# cs42448_breakout.net
KiCad netlist of a schematic drawn in Altium Designer
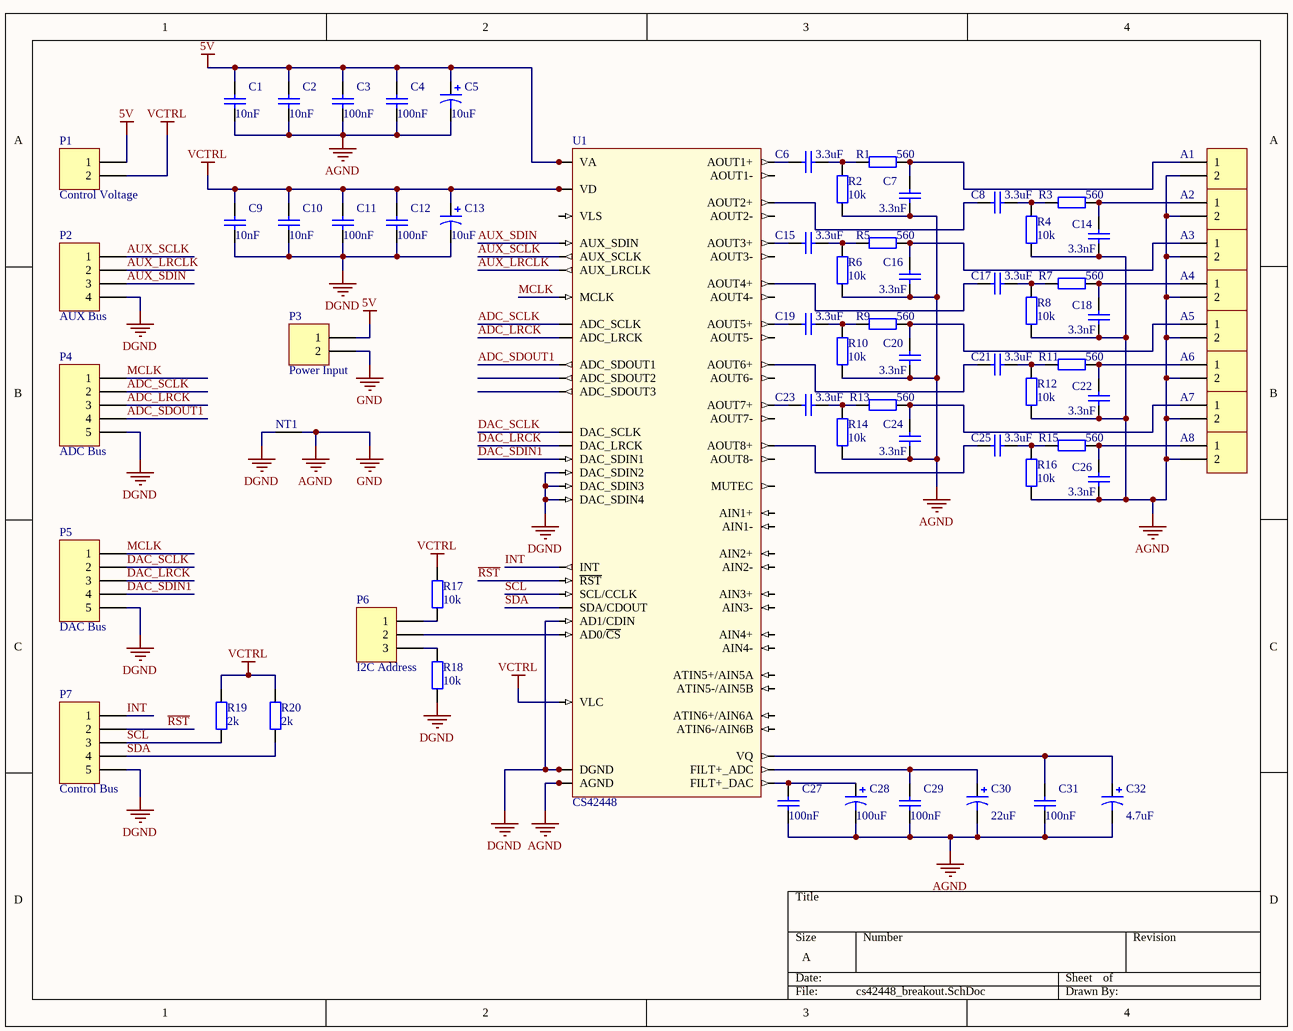
[diagram p0: cs42448_breakout.SchDoc]

(export (version "E")
  (design (tool "Eeschema 10.0.6"))
  (components
    (comp (ref "A1")
      (value "Header 2")
      (footprint "HDR1X2")
      (description "Header, 2-Pin")
      (fields (field (name "PUBLISHER") "Altium Limited"))
      (libsource (lib "") (part "Header 2_1"))
    )
    (comp (ref "A2")
      (value "Header 2")
      (footprint "HDR1X2")
      (description "Header, 2-Pin")
      (fields (field (name "PUBLISHER") "Altium Limited"))
      (libsource (lib "") (part "Header 2_1"))
    )
    (comp (ref "A3")
      (value "Header 2")
      (footprint "HDR1X2")
      (description "Header, 2-Pin")
      (fields (field (name "PUBLISHER") "Altium Limited"))
      (libsource (lib "") (part "Header 2_1"))
    )
    (comp (ref "A4")
      (value "Header 2")
      (footprint "HDR1X2")
      (description "Header, 2-Pin")
      (fields (field (name "PUBLISHER") "Altium Limited"))
      (libsource (lib "") (part "Header 2_1"))
    )
    (comp (ref "A5")
      (value "Header 2")
      (footprint "HDR1X2")
      (description "Header, 2-Pin")
      (fields (field (name "PUBLISHER") "Altium Limited"))
      (libsource (lib "") (part "Header 2_1"))
    )
    (comp (ref "A6")
      (value "Header 2")
      (footprint "HDR1X2")
      (description "Header, 2-Pin")
      (fields (field (name "PUBLISHER") "Altium Limited"))
      (libsource (lib "") (part "Header 2_1"))
    )
    (comp (ref "A7")
      (value "Header 2")
      (footprint "HDR1X2")
      (description "Header, 2-Pin")
      (fields (field (name "PUBLISHER") "Altium Limited"))
      (libsource (lib "") (part "Header 2_1"))
    )
    (comp (ref "A8")
      (value "Header 2")
      (footprint "HDR1X2")
      (description "Header, 2-Pin")
      (fields (field (name "PUBLISHER") "Altium Limited"))
      (libsource (lib "") (part "Header 2_1"))
    )
    (comp (ref "C1")
      (value "10nF")
      (footprint "1608[0603]")
      (description "Capacitor")
      (fields (field (name "Comment") "Cap") (field (name "PUBLISHER") "Altium Limited"))
      (libsource (lib "Miscellaneous Devices") (part "Cap"))
    )
    (comp (ref "C2")
      (value "10nF")
      (footprint "1608[0603]")
      (description "Capacitor")
      (fields (field (name "Comment") "Cap") (field (name "PUBLISHER") "Altium Limited"))
      (libsource (lib "Miscellaneous Devices") (part "Cap"))
    )
    (comp (ref "C3")
      (value "100nF")
      (footprint "1608[0603]")
      (description "Capacitor")
      (fields (field (name "Comment") "Cap") (field (name "PUBLISHER") "Altium Limited"))
      (libsource (lib "Miscellaneous Devices") (part "Cap"))
    )
    (comp (ref "C4")
      (value "100nF")
      (footprint "1608[0603]")
      (description "Capacitor")
      (fields (field (name "Comment") "Cap") (field (name "PUBLISHER") "Altium Limited"))
      (libsource (lib "Miscellaneous Devices") (part "Cap"))
    )
    (comp (ref "C5")
      (value "10uF")
      (footprint "Miscellaneous Devices:CAPR5-4X5")
      (description "Polarized Capacitor (Radial)")
      (fields (field (name "Comment") "Cap Pol1") (field (name "PUBLISHER") "Altium Limited"))
      (libsource (lib "Miscellaneous Devices") (part "Cap Pol1"))
    )
    (comp (ref "C6")
      (value "3.3uF")
      (footprint "1608[0603]")
      (description "Capacitor")
      (fields (field (name "Comment") "Cap") (field (name "PUBLISHER") "Altium Limited"))
      (libsource (lib "Miscellaneous Devices") (part "Cap"))
    )
    (comp (ref "C7")
      (value "3.3nF")
      (footprint "1608[0603]")
      (description "Capacitor")
      (fields (field (name "Comment") "Cap") (field (name "PUBLISHER") "Altium Limited"))
      (libsource (lib "Miscellaneous Devices") (part "Cap"))
    )
    (comp (ref "C8")
      (value "3.3uF")
      (footprint "1608[0603]")
      (description "Capacitor")
      (fields (field (name "Comment") "Cap") (field (name "PUBLISHER") "Altium Limited"))
      (libsource (lib "Miscellaneous Devices") (part "Cap"))
    )
    (comp (ref "C9")
      (value "10nF")
      (footprint "1608[0603]")
      (description "Capacitor")
      (fields (field (name "Comment") "Cap") (field (name "PUBLISHER") "Altium Limited"))
      (libsource (lib "Miscellaneous Devices") (part "Cap"))
    )
    (comp (ref "C10")
      (value "10nF")
      (footprint "1608[0603]")
      (description "Capacitor")
      (fields (field (name "Comment") "Cap") (field (name "PUBLISHER") "Altium Limited"))
      (libsource (lib "Miscellaneous Devices") (part "Cap"))
    )
    (comp (ref "C11")
      (value "100nF")
      (footprint "1608[0603]")
      (description "Capacitor")
      (fields (field (name "Comment") "Cap") (field (name "PUBLISHER") "Altium Limited"))
      (libsource (lib "Miscellaneous Devices") (part "Cap"))
    )
    (comp (ref "C12")
      (value "100nF")
      (footprint "1608[0603]")
      (description "Capacitor")
      (fields (field (name "Comment") "Cap") (field (name "PUBLISHER") "Altium Limited"))
      (libsource (lib "Miscellaneous Devices") (part "Cap"))
    )
    (comp (ref "C13")
      (value "10uF")
      (footprint "Miscellaneous Devices:CAPR5-4X5")
      (description "Polarized Capacitor (Radial)")
      (fields (field (name "Comment") "Cap Pol1") (field (name "PUBLISHER") "Altium Limited"))
      (libsource (lib "Miscellaneous Devices") (part "Cap Pol1"))
    )
    (comp (ref "C14")
      (value "3.3nF")
      (footprint "1608[0603]")
      (description "Capacitor")
      (fields (field (name "Comment") "Cap") (field (name "PUBLISHER") "Altium Limited"))
      (libsource (lib "Miscellaneous Devices") (part "Cap"))
    )
    (comp (ref "C15")
      (value "3.3uF")
      (footprint "1608[0603]")
      (description "Capacitor")
      (fields (field (name "Comment") "Cap") (field (name "PUBLISHER") "Altium Limited"))
      (libsource (lib "Miscellaneous Devices") (part "Cap"))
    )
    (comp (ref "C16")
      (value "3.3nF")
      (footprint "1608[0603]")
      (description "Capacitor")
      (fields (field (name "Comment") "Cap") (field (name "PUBLISHER") "Altium Limited"))
      (libsource (lib "Miscellaneous Devices") (part "Cap"))
    )
    (comp (ref "C17")
      (value "3.3uF")
      (footprint "1608[0603]")
      (description "Capacitor")
      (fields (field (name "Comment") "Cap") (field (name "PUBLISHER") "Altium Limited"))
      (libsource (lib "Miscellaneous Devices") (part "Cap"))
    )
    (comp (ref "C18")
      (value "3.3nF")
      (footprint "1608[0603]")
      (description "Capacitor")
      (fields (field (name "Comment") "Cap") (field (name "PUBLISHER") "Altium Limited"))
      (libsource (lib "Miscellaneous Devices") (part "Cap"))
    )
    (comp (ref "C19")
      (value "3.3uF")
      (footprint "1608[0603]")
      (description "Capacitor")
      (fields (field (name "Comment") "Cap") (field (name "PUBLISHER") "Altium Limited"))
      (libsource (lib "Miscellaneous Devices") (part "Cap"))
    )
    (comp (ref "C20")
      (value "3.3nF")
      (footprint "1608[0603]")
      (description "Capacitor")
      (fields (field (name "Comment") "Cap") (field (name "PUBLISHER") "Altium Limited"))
      (libsource (lib "Miscellaneous Devices") (part "Cap"))
    )
    (comp (ref "C21")
      (value "3.3uF")
      (footprint "1608[0603]")
      (description "Capacitor")
      (fields (field (name "Comment") "Cap") (field (name "PUBLISHER") "Altium Limited"))
      (libsource (lib "Miscellaneous Devices") (part "Cap"))
    )
    (comp (ref "C22")
      (value "3.3nF")
      (footprint "1608[0603]")
      (description "Capacitor")
      (fields (field (name "Comment") "Cap") (field (name "PUBLISHER") "Altium Limited"))
      (libsource (lib "Miscellaneous Devices") (part "Cap"))
    )
    (comp (ref "C23")
      (value "3.3uF")
      (footprint "1608[0603]")
      (description "Capacitor")
      (fields (field (name "Comment") "Cap") (field (name "PUBLISHER") "Altium Limited"))
      (libsource (lib "Miscellaneous Devices") (part "Cap"))
    )
    (comp (ref "C24")
      (value "3.3nF")
      (footprint "1608[0603]")
      (description "Capacitor")
      (fields (field (name "Comment") "Cap") (field (name "PUBLISHER") "Altium Limited"))
      (libsource (lib "Miscellaneous Devices") (part "Cap"))
    )
    (comp (ref "C25")
      (value "3.3uF")
      (footprint "1608[0603]")
      (description "Capacitor")
      (fields (field (name "Comment") "Cap") (field (name "PUBLISHER") "Altium Limited"))
      (libsource (lib "Miscellaneous Devices") (part "Cap"))
    )
    (comp (ref "C26")
      (value "3.3nF")
      (footprint "1608[0603]")
      (description "Capacitor")
      (fields (field (name "Comment") "Cap") (field (name "PUBLISHER") "Altium Limited"))
      (libsource (lib "Miscellaneous Devices") (part "Cap"))
    )
    (comp (ref "C27")
      (value "100nF")
      (footprint "1608[0603]")
      (description "Capacitor")
      (fields (field (name "Comment") "Cap") (field (name "PUBLISHER") "Altium Limited"))
      (libsource (lib "Miscellaneous Devices") (part "Cap"))
    )
    (comp (ref "C28")
      (value "100uF")
      (footprint "Miscellaneous Devices:CAPR5-4X5")
      (description "Polarized Capacitor (Radial)")
      (fields (field (name "Comment") "Cap Pol1") (field (name "PUBLISHER") "Altium Limited"))
      (libsource (lib "Miscellaneous Devices") (part "Cap Pol1"))
    )
    (comp (ref "C29")
      (value "100nF")
      (footprint "1608[0603]")
      (description "Capacitor")
      (fields (field (name "Comment") "Cap") (field (name "PUBLISHER") "Altium Limited"))
      (libsource (lib "Miscellaneous Devices") (part "Cap"))
    )
    (comp (ref "C30")
      (value "22uF")
      (footprint "Miscellaneous Devices:CAPR5-4X5")
      (description "Polarized Capacitor (Radial)")
      (fields (field (name "Comment") "Cap Pol1") (field (name "PUBLISHER") "Altium Limited"))
      (libsource (lib "Miscellaneous Devices") (part "Cap Pol1"))
    )
    (comp (ref "C31")
      (value "100nF")
      (footprint "1608[0603]")
      (description "Capacitor")
      (fields (field (name "Comment") "Cap") (field (name "PUBLISHER") "Altium Limited"))
      (libsource (lib "Miscellaneous Devices") (part "Cap"))
    )
    (comp (ref "C32")
      (value "4.7uF")
      (footprint "Miscellaneous Devices:CAPR5-4X5")
      (description "Polarized Capacitor (Radial)")
      (fields (field (name "Comment") "Cap Pol1") (field (name "PUBLISHER") "Altium Limited"))
      (libsource (lib "Miscellaneous Devices") (part "Cap Pol1"))
    )
    (comp (ref "NT1")
      (value "Net Tie")
      (footprint "1608[0603] Net Tie")
      (libsource (lib "cs42448_breakout") (part "Net Tie"))
    )
    (comp (ref "P1")
      (value "Control Voltage")
      (footprint "HDR1X2")
      (description "Header, 2-Pin")
      (fields (field (name "PUBLISHER") "Altium Limited"))
      (libsource (lib "Miscellaneous Connectors") (part "Header 2"))
    )
    (comp (ref "P2")
      (value "AUX Bus")
      (footprint "HDR1X4")
      (description "Header, 4-Pin")
      (fields (field (name "PUBLISHER") "Altium Limited"))
      (libsource (lib "Miscellaneous Connectors") (part "Header 4"))
    )
    (comp (ref "P3")
      (value "Power Input")
      (footprint "HDR1X2")
      (description "Header, 2-Pin")
      (fields (field (name "PUBLISHER") "Altium Limited"))
      (libsource (lib "Miscellaneous Connectors") (part "Header 2"))
    )
    (comp (ref "P4")
      (value "ADC Bus")
      (footprint "HDR1X5")
      (description "Header, 5-Pin")
      (fields (field (name "PUBLISHER") "Altium Limited"))
      (libsource (lib "Miscellaneous Connectors") (part "Header 5"))
    )
    (comp (ref "P5")
      (value "DAC Bus")
      (footprint "HDR1X5")
      (description "Header, 5-Pin")
      (fields (field (name "PUBLISHER") "Altium Limited"))
      (libsource (lib "Miscellaneous Connectors") (part "Header 5"))
    )
    (comp (ref "P6")
      (value "I2C Address")
      (footprint "HDR1X3")
      (description "Header, 3-Pin")
      (fields (field (name "PUBLISHER") "Altium Limited"))
      (libsource (lib "Miscellaneous Connectors") (part "Header 3"))
    )
    (comp (ref "P7")
      (value "Control Bus")
      (footprint "HDR1X5")
      (description "Header, 5-Pin")
      (fields (field (name "PUBLISHER") "Altium Limited"))
      (libsource (lib "Miscellaneous Connectors") (part "Header 5"))
    )
    (comp (ref "R1")
      (value "560")
      (footprint "1608[0603]")
      (description "Resistor")
      (fields (field (name "Comment") "Res2") (field (name "PUBLISHER") "Altium Limited"))
      (libsource (lib "") (part "Res2_1"))
    )
    (comp (ref "R2")
      (value "10k")
      (footprint "1608[0603]")
      (description "Resistor")
      (fields (field (name "Comment") "Res2") (field (name "PUBLISHER") "Altium Limited"))
      (libsource (lib "Miscellaneous Devices") (part "Res2"))
    )
    (comp (ref "R3")
      (value "560")
      (footprint "1608[0603]")
      (description "Resistor")
      (fields (field (name "Comment") "Res2") (field (name "PUBLISHER") "Altium Limited"))
      (libsource (lib "") (part "Res2_1"))
    )
    (comp (ref "R4")
      (value "10k")
      (footprint "1608[0603]")
      (description "Resistor")
      (fields (field (name "Comment") "Res2") (field (name "PUBLISHER") "Altium Limited"))
      (libsource (lib "Miscellaneous Devices") (part "Res2"))
    )
    (comp (ref "R5")
      (value "560")
      (footprint "1608[0603]")
      (description "Resistor")
      (fields (field (name "Comment") "Res2") (field (name "PUBLISHER") "Altium Limited"))
      (libsource (lib "") (part "Res2_1"))
    )
    (comp (ref "R6")
      (value "10k")
      (footprint "1608[0603]")
      (description "Resistor")
      (fields (field (name "Comment") "Res2") (field (name "PUBLISHER") "Altium Limited"))
      (libsource (lib "Miscellaneous Devices") (part "Res2"))
    )
    (comp (ref "R7")
      (value "560")
      (footprint "1608[0603]")
      (description "Resistor")
      (fields (field (name "Comment") "Res2") (field (name "PUBLISHER") "Altium Limited"))
      (libsource (lib "") (part "Res2_1"))
    )
    (comp (ref "R8")
      (value "10k")
      (footprint "1608[0603]")
      (description "Resistor")
      (fields (field (name "Comment") "Res2") (field (name "PUBLISHER") "Altium Limited"))
      (libsource (lib "Miscellaneous Devices") (part "Res2"))
    )
    (comp (ref "R9")
      (value "560")
      (footprint "1608[0603]")
      (description "Resistor")
      (fields (field (name "Comment") "Res2") (field (name "PUBLISHER") "Altium Limited"))
      (libsource (lib "") (part "Res2_1"))
    )
    (comp (ref "R10")
      (value "10k")
      (footprint "1608[0603]")
      (description "Resistor")
      (fields (field (name "Comment") "Res2") (field (name "PUBLISHER") "Altium Limited"))
      (libsource (lib "Miscellaneous Devices") (part "Res2"))
    )
    (comp (ref "R11")
      (value "560")
      (footprint "1608[0603]")
      (description "Resistor")
      (fields (field (name "Comment") "Res2") (field (name "PUBLISHER") "Altium Limited"))
      (libsource (lib "") (part "Res2_1"))
    )
    (comp (ref "R12")
      (value "10k")
      (footprint "1608[0603]")
      (description "Resistor")
      (fields (field (name "Comment") "Res2") (field (name "PUBLISHER") "Altium Limited"))
      (libsource (lib "Miscellaneous Devices") (part "Res2"))
    )
    (comp (ref "R13")
      (value "560")
      (footprint "1608[0603]")
      (description "Resistor")
      (fields (field (name "Comment") "Res2") (field (name "PUBLISHER") "Altium Limited"))
      (libsource (lib "") (part "Res2_1"))
    )
    (comp (ref "R14")
      (value "10k")
      (footprint "1608[0603]")
      (description "Resistor")
      (fields (field (name "Comment") "Res2") (field (name "PUBLISHER") "Altium Limited"))
      (libsource (lib "Miscellaneous Devices") (part "Res2"))
    )
    (comp (ref "R15")
      (value "560")
      (footprint "1608[0603]")
      (description "Resistor")
      (fields (field (name "Comment") "Res2") (field (name "PUBLISHER") "Altium Limited"))
      (libsource (lib "") (part "Res2_1"))
    )
    (comp (ref "R16")
      (value "10k")
      (footprint "1608[0603]")
      (description "Resistor")
      (fields (field (name "Comment") "Res2") (field (name "PUBLISHER") "Altium Limited"))
      (libsource (lib "Miscellaneous Devices") (part "Res2"))
    )
    (comp (ref "R17")
      (value "10k")
      (footprint "1608[0603]")
      (description "Resistor")
      (fields (field (name "Comment") "Res2") (field (name "PUBLISHER") "Altium Limited"))
      (libsource (lib "Miscellaneous Devices") (part "Res2"))
    )
    (comp (ref "R18")
      (value "10k")
      (footprint "1608[0603]")
      (description "Resistor")
      (fields (field (name "Comment") "Res2") (field (name "PUBLISHER") "Altium Limited"))
      (libsource (lib "Miscellaneous Devices") (part "Res2"))
    )
    (comp (ref "R19")
      (value "2k")
      (footprint "1608[0603]")
      (description "Resistor")
      (fields (field (name "Comment") "Res2") (field (name "PUBLISHER") "Altium Limited"))
      (libsource (lib "Miscellaneous Devices") (part "Res2"))
    )
    (comp (ref "R20")
      (value "2k")
      (footprint "1608[0603]")
      (description "Resistor")
      (fields (field (name "Comment") "Res2") (field (name "PUBLISHER") "Altium Limited"))
      (libsource (lib "Miscellaneous Devices") (part "Res2"))
    )
    (comp (ref "U1")
      (value "CS42448")
      (footprint "64L-LQFP")
      (description "108 dB, 192 kHz 6-In, 8-Out CODEC")
      (libsource (lib "cs42448_breakout") (part "CS42448"))
    )
  )
  (nets
    (net (code "1") (name "/ADC_LRCK") (class "Default")
      (node (ref "P4") (pin "3") (pinfunction "3_3") (pintype "passive"))
      (node (ref "U1") (pin "5") (pinfunction "ADC_LRCK_5") (pintype "bidirectional"))
    )
    (net (code "2") (name "/ADC_SCLK") (class "Default")
      (node (ref "P4") (pin "2") (pinfunction "2_2") (pintype "passive"))
      (node (ref "U1") (pin "9") (pinfunction "ADC_SCLK_9") (pintype "bidirectional"))
    )
    (net (code "3") (name "/ADC_SDOUT1") (class "Default")
      (node (ref "P4") (pin "4") (pinfunction "4_4") (pintype "passive"))
      (node (ref "U1") (pin "13") (pinfunction "ADC_SDOUT1_13") (pintype "output"))
    )
    (net (code "4") (name "/AUX_LRCLK") (class "Default")
      (node (ref "P2") (pin "2") (pinfunction "2_2") (pintype "passive"))
      (node (ref "U1") (pin "20") (pinfunction "AUX_LRCLK_20") (pintype "output"))
    )
    (net (code "5") (name "/AUX_SCLK") (class "Default")
      (node (ref "P2") (pin "1") (pinfunction "1_1") (pintype "passive"))
      (node (ref "U1") (pin "21") (pinfunction "AUX_SCLK_21") (pintype "output"))
    )
    (net (code "6") (name "/AUX_SDIN") (class "Default")
      (node (ref "P2") (pin "3") (pinfunction "3_3") (pintype "passive"))
      (node (ref "U1") (pin "22") (pinfunction "AUX_SDIN_22") (pintype "input"))
    )
    (net (code "7") (name "/DAC_LRCK") (class "Default")
      (node (ref "P5") (pin "3") (pinfunction "3_3") (pintype "passive"))
      (node (ref "U1") (pin "19") (pinfunction "DAC_LRCK_19") (pintype "bidirectional"))
    )
    (net (code "8") (name "/DAC_SCLK") (class "Default")
      (node (ref "P5") (pin "2") (pinfunction "2_2") (pintype "passive"))
      (node (ref "U1") (pin "18") (pinfunction "DAC_SCLK_18") (pintype "bidirectional"))
    )
    (net (code "9") (name "/DAC_SDIN1") (class "Default")
      (node (ref "P5") (pin "4") (pinfunction "4_4") (pintype "passive"))
      (node (ref "U1") (pin "17") (pinfunction "DAC_SDIN1_17") (pintype "input"))
    )
    (net (code "10") (name "/INT") (class "Default")
      (node (ref "P7") (pin "1") (pinfunction "1_1") (pintype "passive"))
      (node (ref "U1") (pin "61") (pinfunction "INT_61") (pintype "output"))
    )
    (net (code "11") (name "/MCLK") (class "Default")
      (node (ref "P4") (pin "1") (pinfunction "1_1") (pintype "passive"))
      (node (ref "P5") (pin "1") (pinfunction "1_1") (pintype "passive"))
      (node (ref "U1") (pin "10") (pinfunction "MCLK_10") (pintype "input"))
    )
    (net (code "12") (name "/SCL") (class "Default")
      (node (ref "P7") (pin "3") (pinfunction "3_3") (pintype "passive"))
      (node (ref "R19") (pin "2") (pinfunction "2_2") (pintype "passive"))
      (node (ref "U1") (pin "63") (pinfunction "SCL/CCLK_63") (pintype "input"))
    )
    (net (code "13") (name "/SDA") (class "Default")
      (node (ref "P7") (pin "4") (pinfunction "4_4") (pintype "passive"))
      (node (ref "R20") (pin "2") (pinfunction "2_2") (pintype "passive"))
      (node (ref "U1") (pin "64") (pinfunction "SDA/CDOUT_64") (pintype "bidirectional"))
    )
    (net (code "14") (name "/~{RST}") (class "Default")
      (node (ref "P7") (pin "2") (pinfunction "2_2") (pintype "passive"))
      (node (ref "U1") (pin "3") (pinfunction "~{RST}_3") (pintype "input"))
    )
    (net (code "15") (name "5V") (class "Default")
      (node (ref "C1") (pin "2") (pinfunction "2_2") (pintype "passive"))
      (node (ref "C2") (pin "2") (pinfunction "2_2") (pintype "passive"))
      (node (ref "C3") (pin "2") (pinfunction "2_2") (pintype "passive"))
      (node (ref "C4") (pin "2") (pinfunction "2_2") (pintype "passive"))
      (node (ref "C5") (pin "1") (pinfunction "1_1") (pintype "passive"))
      (node (ref "P1") (pin "1") (pinfunction "1_1") (pintype "passive"))
      (node (ref "P3") (pin "1") (pinfunction "1_1") (pintype "passive"))
      (node (ref "U1") (pin "44") (pinfunction "VA_44") (pintype "power_in"))
      (node (ref "U1") (pin "53") (pinfunction "VA_53") (pintype "power_in"))
    )
    (net (code "16") (name "AGND") (class "Default")
      (node (ref "A1") (pin "2") (pinfunction "2_2") (pintype "passive"))
      (node (ref "A2") (pin "2") (pinfunction "2_2") (pintype "passive"))
      (node (ref "A3") (pin "2") (pinfunction "2_2") (pintype "passive"))
      (node (ref "A4") (pin "2") (pinfunction "2_2") (pintype "passive"))
      (node (ref "A5") (pin "2") (pinfunction "2_2") (pintype "passive"))
      (node (ref "A6") (pin "2") (pinfunction "2_2") (pintype "passive"))
      (node (ref "A7") (pin "2") (pinfunction "2_2") (pintype "passive"))
      (node (ref "A8") (pin "2") (pinfunction "2_2") (pintype "passive"))
      (node (ref "C1") (pin "1") (pinfunction "1_1") (pintype "passive"))
      (node (ref "C14") (pin "1") (pinfunction "1_1") (pintype "passive"))
      (node (ref "C16") (pin "1") (pinfunction "1_1") (pintype "passive"))
      (node (ref "C18") (pin "1") (pinfunction "1_1") (pintype "passive"))
      (node (ref "C2") (pin "1") (pinfunction "1_1") (pintype "passive"))
      (node (ref "C20") (pin "1") (pinfunction "1_1") (pintype "passive"))
      (node (ref "C22") (pin "1") (pinfunction "1_1") (pintype "passive"))
      (node (ref "C24") (pin "1") (pinfunction "1_1") (pintype "passive"))
      (node (ref "C26") (pin "1") (pinfunction "1_1") (pintype "passive"))
      (node (ref "C27") (pin "1") (pinfunction "1_1") (pintype "passive"))
      (node (ref "C28") (pin "2") (pinfunction "2_2") (pintype "passive"))
      (node (ref "C29") (pin "1") (pinfunction "1_1") (pintype "passive"))
      (node (ref "C3") (pin "1") (pinfunction "1_1") (pintype "passive"))
      (node (ref "C30") (pin "2") (pinfunction "2_2") (pintype "passive"))
      (node (ref "C31") (pin "1") (pinfunction "1_1") (pintype "passive"))
      (node (ref "C32") (pin "2") (pinfunction "2_2") (pintype "passive"))
      (node (ref "C4") (pin "1") (pinfunction "1_1") (pintype "passive"))
      (node (ref "C5") (pin "2") (pinfunction "2_2") (pintype "passive"))
      (node (ref "C7") (pin "1") (pinfunction "1_1") (pintype "passive"))
      (node (ref "NT1") (pin "2") (pinfunction "2_2") (pintype "passive"))
      (node (ref "P3") (pin "2") (pinfunction "2_2") (pintype "passive"))
      (node (ref "R10") (pin "2") (pinfunction "2_2") (pintype "passive"))
      (node (ref "R12") (pin "2") (pinfunction "2_2") (pintype "passive"))
      (node (ref "R14") (pin "2") (pinfunction "2_2") (pintype "passive"))
      (node (ref "R16") (pin "2") (pinfunction "2_2") (pintype "passive"))
      (node (ref "R2") (pin "2") (pinfunction "2_2") (pintype "passive"))
      (node (ref "R4") (pin "2") (pinfunction "2_2") (pintype "passive"))
      (node (ref "R6") (pin "2") (pinfunction "2_2") (pintype "passive"))
      (node (ref "R8") (pin "2") (pinfunction "2_2") (pintype "passive"))
      (node (ref "U1") (pin "42") (pinfunction "AGND_42") (pintype "power_in"))
      (node (ref "U1") (pin "56") (pinfunction "AGND_56") (pintype "power_in"))
    )
    (net (code "17") (name "DGND") (class "Default")
      (node (ref "C10") (pin "1") (pinfunction "1_1") (pintype "passive"))
      (node (ref "C11") (pin "1") (pinfunction "1_1") (pintype "passive"))
      (node (ref "C12") (pin "1") (pinfunction "1_1") (pintype "passive"))
      (node (ref "C13") (pin "2") (pinfunction "2_2") (pintype "passive"))
      (node (ref "C9") (pin "1") (pinfunction "1_1") (pintype "passive"))
      (node (ref "NT1") (pin "1") (pintype "passive"))
      (node (ref "P2") (pin "4") (pinfunction "4_4") (pintype "passive"))
      (node (ref "P4") (pin "5") (pinfunction "5_5") (pintype "passive"))
      (node (ref "P5") (pin "5") (pinfunction "5_5") (pintype "passive"))
      (node (ref "P7") (pin "5") (pinfunction "5_5") (pintype "passive"))
      (node (ref "R18") (pin "2") (pinfunction "2_2") (pintype "passive"))
      (node (ref "U1") (pin "14") (pinfunction "DAC_SDIN4_14") (pintype "input"))
      (node (ref "U1") (pin "15") (pinfunction "DAC_SDIN3_15") (pintype "input"))
      (node (ref "U1") (pin "16") (pinfunction "DAC_SDIN2_16") (pintype "input"))
      (node (ref "U1") (pin "2") (pinfunction "AD1/CDIN_2") (pintype "input"))
      (node (ref "U1") (pin "23") (pinfunction "DGND_23") (pintype "power_in"))
      (node (ref "U1") (pin "62") (pinfunction "DGND_62") (pintype "power_in"))
      (node (ref "U1") (pin "7") (pinfunction "DGND_7") (pintype "power_in"))
    )
    (net (code "18") (name "Net-(A1-Pad1)") (class "Default")
      (node (ref "A1") (pin "1") (pinfunction "1_1") (pintype "passive"))
      (node (ref "C7") (pin "2") (pinfunction "2_2") (pintype "passive"))
      (node (ref "R1") (pin "1") (pinfunction "1_1") (pintype "passive"))
    )
    (net (code "19") (name "Net-(A2-Pad1)") (class "Default")
      (node (ref "A2") (pin "1") (pinfunction "1_1") (pintype "passive"))
      (node (ref "C14") (pin "2") (pinfunction "2_2") (pintype "passive"))
      (node (ref "R3") (pin "1") (pinfunction "1_1") (pintype "passive"))
    )
    (net (code "20") (name "Net-(A3-Pad1)") (class "Default")
      (node (ref "A3") (pin "1") (pinfunction "1_1") (pintype "passive"))
      (node (ref "C16") (pin "2") (pinfunction "2_2") (pintype "passive"))
      (node (ref "R5") (pin "1") (pinfunction "1_1") (pintype "passive"))
    )
    (net (code "21") (name "Net-(A4-Pad1)") (class "Default")
      (node (ref "A4") (pin "1") (pinfunction "1_1") (pintype "passive"))
      (node (ref "C18") (pin "2") (pinfunction "2_2") (pintype "passive"))
      (node (ref "R7") (pin "1") (pinfunction "1_1") (pintype "passive"))
    )
    (net (code "22") (name "Net-(A5-Pad1)") (class "Default")
      (node (ref "A5") (pin "1") (pinfunction "1_1") (pintype "passive"))
      (node (ref "C20") (pin "2") (pinfunction "2_2") (pintype "passive"))
      (node (ref "R9") (pin "1") (pinfunction "1_1") (pintype "passive"))
    )
    (net (code "23") (name "Net-(A6-Pad1)") (class "Default")
      (node (ref "A6") (pin "1") (pinfunction "1_1") (pintype "passive"))
      (node (ref "C22") (pin "2") (pinfunction "2_2") (pintype "passive"))
      (node (ref "R11") (pin "1") (pinfunction "1_1") (pintype "passive"))
    )
    (net (code "24") (name "Net-(A7-Pad1)") (class "Default")
      (node (ref "A7") (pin "1") (pinfunction "1_1") (pintype "passive"))
      (node (ref "C24") (pin "2") (pinfunction "2_2") (pintype "passive"))
      (node (ref "R13") (pin "1") (pinfunction "1_1") (pintype "passive"))
    )
    (net (code "25") (name "Net-(A8-Pad1)") (class "Default")
      (node (ref "A8") (pin "1") (pinfunction "1_1") (pintype "passive"))
      (node (ref "C26") (pin "2") (pinfunction "2_2") (pintype "passive"))
      (node (ref "R15") (pin "1") (pinfunction "1_1") (pintype "passive"))
    )
    (net (code "26") (name "Net-(C6-Pad1)") (class "Default")
      (node (ref "C6") (pin "1") (pinfunction "1_1") (pintype "passive"))
      (node (ref "R1") (pin "2") (pinfunction "2_2") (pintype "passive"))
      (node (ref "R2") (pin "1") (pinfunction "1_1") (pintype "passive"))
    )
    (net (code "27") (name "Net-(C8-Pad1)") (class "Default")
      (node (ref "C8") (pin "1") (pinfunction "1_1") (pintype "passive"))
      (node (ref "R3") (pin "2") (pinfunction "2_2") (pintype "passive"))
      (node (ref "R4") (pin "1") (pinfunction "1_1") (pintype "passive"))
    )
    (net (code "28") (name "Net-(C15-Pad1)") (class "Default")
      (node (ref "C15") (pin "1") (pinfunction "1_1") (pintype "passive"))
      (node (ref "R5") (pin "2") (pinfunction "2_2") (pintype "passive"))
      (node (ref "R6") (pin "1") (pinfunction "1_1") (pintype "passive"))
    )
    (net (code "29") (name "Net-(C17-Pad1)") (class "Default")
      (node (ref "C17") (pin "1") (pinfunction "1_1") (pintype "passive"))
      (node (ref "R7") (pin "2") (pinfunction "2_2") (pintype "passive"))
      (node (ref "R8") (pin "1") (pinfunction "1_1") (pintype "passive"))
    )
    (net (code "30") (name "Net-(C19-Pad1)") (class "Default")
      (node (ref "C19") (pin "1") (pinfunction "1_1") (pintype "passive"))
      (node (ref "R10") (pin "1") (pinfunction "1_1") (pintype "passive"))
      (node (ref "R9") (pin "2") (pinfunction "2_2") (pintype "passive"))
    )
    (net (code "31") (name "Net-(C21-Pad1)") (class "Default")
      (node (ref "C21") (pin "1") (pinfunction "1_1") (pintype "passive"))
      (node (ref "R11") (pin "2") (pinfunction "2_2") (pintype "passive"))
      (node (ref "R12") (pin "1") (pinfunction "1_1") (pintype "passive"))
    )
    (net (code "32") (name "Net-(C23-Pad1)") (class "Default")
      (node (ref "C23") (pin "1") (pinfunction "1_1") (pintype "passive"))
      (node (ref "R13") (pin "2") (pinfunction "2_2") (pintype "passive"))
      (node (ref "R14") (pin "1") (pinfunction "1_1") (pintype "passive"))
    )
    (net (code "33") (name "Net-(C25-Pad1)") (class "Default")
      (node (ref "C25") (pin "1") (pinfunction "1_1") (pintype "passive"))
      (node (ref "R15") (pin "2") (pinfunction "2_2") (pintype "passive"))
      (node (ref "R16") (pin "1") (pinfunction "1_1") (pintype "passive"))
    )
    (net (code "34") (name "Net-(P6-Pad1)") (class "Default")
      (node (ref "P6") (pin "1") (pinfunction "1_1") (pintype "passive"))
      (node (ref "R17") (pin "2") (pinfunction "2_2") (pintype "passive"))
    )
    (net (code "35") (name "Net-(P6-Pad3)") (class "Default")
      (node (ref "P6") (pin "3") (pinfunction "3_3") (pintype "passive"))
      (node (ref "R18") (pin "1") (pinfunction "1_1") (pintype "passive"))
    )
    (net (code "36") (name "Net-(U1-AD0{slash}~{CS})") (class "Default")
      (node (ref "P6") (pin "2") (pinfunction "2_2") (pintype "passive"))
      (node (ref "U1") (pin "1") (pinfunction "AD0/~{CS}_1") (pintype "input"))
    )
    (net (code "37") (name "Net-(U1-AOUT1+)") (class "Default")
      (node (ref "C6") (pin "2") (pinfunction "2_2") (pintype "passive"))
      (node (ref "U1") (pin "26") (pinfunction "AOUT1+_26") (pintype "output"))
    )
    (net (code "38") (name "Net-(U1-AOUT2+)") (class "Default")
      (node (ref "C8") (pin "2") (pinfunction "2_2") (pintype "passive"))
      (node (ref "U1") (pin "27") (pinfunction "AOUT2+_27") (pintype "output"))
    )
    (net (code "39") (name "Net-(U1-AOUT3+)") (class "Default")
      (node (ref "C15") (pin "2") (pinfunction "2_2") (pintype "passive"))
      (node (ref "U1") (pin "30") (pinfunction "AOUT3+_30") (pintype "output"))
    )
    (net (code "40") (name "Net-(U1-AOUT4+)") (class "Default")
      (node (ref "C17") (pin "2") (pinfunction "2_2") (pintype "passive"))
      (node (ref "U1") (pin "31") (pinfunction "AOUT4+_31") (pintype "output"))
    )
    (net (code "41") (name "Net-(U1-AOUT5+)") (class "Default")
      (node (ref "C19") (pin "2") (pinfunction "2_2") (pintype "passive"))
      (node (ref "U1") (pin "34") (pinfunction "AOUT5+_34") (pintype "output"))
    )
    (net (code "42") (name "Net-(U1-AOUT6+)") (class "Default")
      (node (ref "C21") (pin "2") (pinfunction "2_2") (pintype "passive"))
      (node (ref "U1") (pin "36") (pinfunction "AOUT6+_36") (pintype "output"))
    )
    (net (code "43") (name "Net-(U1-AOUT7+)") (class "Default")
      (node (ref "C23") (pin "2") (pinfunction "2_2") (pintype "passive"))
      (node (ref "U1") (pin "39") (pinfunction "AOUT7+_39") (pintype "output"))
    )
    (net (code "44") (name "Net-(U1-AOUT8+)") (class "Default")
      (node (ref "C25") (pin "2") (pinfunction "2_2") (pintype "passive"))
      (node (ref "U1") (pin "40") (pinfunction "AOUT8+_40") (pintype "output"))
    )
    (net (code "45") (name "Net-(U1-FILT+_ADC)") (class "Default")
      (node (ref "C29") (pin "2") (pinfunction "2_2") (pintype "passive"))
      (node (ref "C30") (pin "1") (pinfunction "1_1") (pintype "passive"))
      (node (ref "U1") (pin "55") (pinfunction "FILT+_ADC_55") (pintype "output"))
    )
    (net (code "46") (name "Net-(U1-FILT+_DAC)") (class "Default")
      (node (ref "C27") (pin "2") (pinfunction "2_2") (pintype "passive"))
      (node (ref "C28") (pin "1") (pinfunction "1_1") (pintype "passive"))
      (node (ref "U1") (pin "54") (pinfunction "FILT+_DAC_54") (pintype "output"))
    )
    (net (code "47") (name "Net-(U1-VQ)") (class "Default")
      (node (ref "C31") (pin "2") (pinfunction "2_2") (pintype "passive"))
      (node (ref "C32") (pin "1") (pinfunction "1_1") (pintype "passive"))
      (node (ref "U1") (pin "43") (pinfunction "VQ_43") (pintype "output"))
    )
    (net (code "48") (name "VCTRL") (class "Default")
      (node (ref "C10") (pin "2") (pinfunction "2_2") (pintype "passive"))
      (node (ref "C11") (pin "2") (pinfunction "2_2") (pintype "passive"))
      (node (ref "C12") (pin "2") (pinfunction "2_2") (pintype "passive"))
      (node (ref "C13") (pin "1") (pinfunction "1_1") (pintype "passive"))
      (node (ref "C9") (pin "2") (pinfunction "2_2") (pintype "passive"))
      (node (ref "P1") (pin "2") (pinfunction "2_2") (pintype "passive"))
      (node (ref "R17") (pin "1") (pinfunction "1_1") (pintype "passive"))
      (node (ref "R19") (pin "1") (pinfunction "1_1") (pintype "passive"))
      (node (ref "R20") (pin "1") (pinfunction "1_1") (pintype "passive"))
      (node (ref "U1") (pin "24") (pinfunction "VD_24") (pintype "power_in"))
      (node (ref "U1") (pin "4") (pinfunction "VLC_4") (pintype "input"))
      (node (ref "U1") (pin "6") (pinfunction "VD_6") (pintype "power_in"))
    )
    (net (code "49") (name "unconnected-(U1-ADC_SDOUT2-Pad12)") (class "Default")
      (node (ref "U1") (pin "12") (pinfunction "ADC_SDOUT2_12") (pintype "output"))
    )
    (net (code "50") (name "unconnected-(U1-ADC_SDOUT3-Pad11)") (class "Default")
      (node (ref "U1") (pin "11") (pinfunction "ADC_SDOUT3_11") (pintype "output"))
    )
    (net (code "51") (name "unconnected-(U1-AIN1+-Pad46)") (class "Default")
      (node (ref "U1") (pin "46") (pinfunction "AIN1+_46") (pintype "input"))
    )
    (net (code "52") (name "unconnected-(U1-AIN1--Pad45)") (class "Default")
      (node (ref "U1") (pin "45") (pinfunction "AIN1-_45") (pintype "input"))
    )
    (net (code "53") (name "unconnected-(U1-AIN2+-Pad48)") (class "Default")
      (node (ref "U1") (pin "48") (pinfunction "AIN2+_48") (pintype "input"))
    )
    (net (code "54") (name "unconnected-(U1-AIN2--Pad47)") (class "Default")
      (node (ref "U1") (pin "47") (pinfunction "AIN2-_47") (pintype "input"))
    )
    (net (code "55") (name "unconnected-(U1-AIN3+-Pad50)") (class "Default")
      (node (ref "U1") (pin "50") (pinfunction "AIN3+_50") (pintype "input"))
    )
    (net (code "56") (name "unconnected-(U1-AIN3--Pad49)") (class "Default")
      (node (ref "U1") (pin "49") (pinfunction "AIN3-_49") (pintype "input"))
    )
    (net (code "57") (name "unconnected-(U1-AIN4+-Pad52)") (class "Default")
      (node (ref "U1") (pin "52") (pinfunction "AIN4+_52") (pintype "input"))
    )
    (net (code "58") (name "unconnected-(U1-AIN4--Pad51)") (class "Default")
      (node (ref "U1") (pin "51") (pinfunction "AIN4-_51") (pintype "input"))
    )
    (net (code "59") (name "unconnected-(U1-AOUT1--Pad25)") (class "Default")
      (node (ref "U1") (pin "25") (pinfunction "AOUT1-_25") (pintype "output"))
    )
    (net (code "60") (name "unconnected-(U1-AOUT2--Pad28)") (class "Default")
      (node (ref "U1") (pin "28") (pinfunction "AOUT2-_28") (pintype "output"))
    )
    (net (code "61") (name "unconnected-(U1-AOUT3--Pad29)") (class "Default")
      (node (ref "U1") (pin "29") (pinfunction "AOUT3-_29") (pintype "output"))
    )
    (net (code "62") (name "unconnected-(U1-AOUT4--Pad32)") (class "Default")
      (node (ref "U1") (pin "32") (pinfunction "AOUT4-_32") (pintype "output"))
    )
    (net (code "63") (name "unconnected-(U1-AOUT5--Pad33)") (class "Default")
      (node (ref "U1") (pin "33") (pinfunction "AOUT5-_33") (pintype "output"))
    )
    (net (code "64") (name "unconnected-(U1-AOUT6--Pad37)") (class "Default")
      (node (ref "U1") (pin "37") (pinfunction "AOUT6-_37") (pintype "output"))
    )
    (net (code "65") (name "unconnected-(U1-AOUT7--Pad38)") (class "Default")
      (node (ref "U1") (pin "38") (pinfunction "AOUT7-_38") (pintype "output"))
    )
    (net (code "66") (name "unconnected-(U1-AOUT8--Pad41)") (class "Default")
      (node (ref "U1") (pin "41") (pinfunction "AOUT8-_41") (pintype "output"))
    )
    (net (code "67") (name "unconnected-(U1-ATIN5+{slash}AIN5A-Pad58)") (class "Default")
      (node (ref "U1") (pin "58") (pinfunction "ATIN5+/AIN5A_58") (pintype "input"))
    )
    (net (code "68") (name "unconnected-(U1-ATIN5-{slash}AIN5B-Pad57)") (class "Default")
      (node (ref "U1") (pin "57") (pinfunction "ATIN5-/AIN5B_57") (pintype "input"))
    )
    (net (code "69") (name "unconnected-(U1-ATIN6+{slash}AIN6A-Pad60)") (class "Default")
      (node (ref "U1") (pin "60") (pinfunction "ATIN6+/AIN6A_60") (pintype "input"))
    )
    (net (code "70") (name "unconnected-(U1-ATIN6-{slash}AIN6B-Pad59)") (class "Default")
      (node (ref "U1") (pin "59") (pinfunction "ATIN6-/AIN6B_59") (pintype "input"))
    )
    (net (code "71") (name "unconnected-(U1-MUTEC-Pad35)") (class "Default")
      (node (ref "U1") (pin "35") (pinfunction "MUTEC_35") (pintype "output"))
    )
    (net (code "72") (name "unconnected-(U1-VLS-Pad8)") (class "Default")
      (node (ref "U1") (pin "8") (pinfunction "VLS_8") (pintype "input"))
    )
  )
)
